# vac.net
KiCad netlist of a schematic drawn in EAGLE
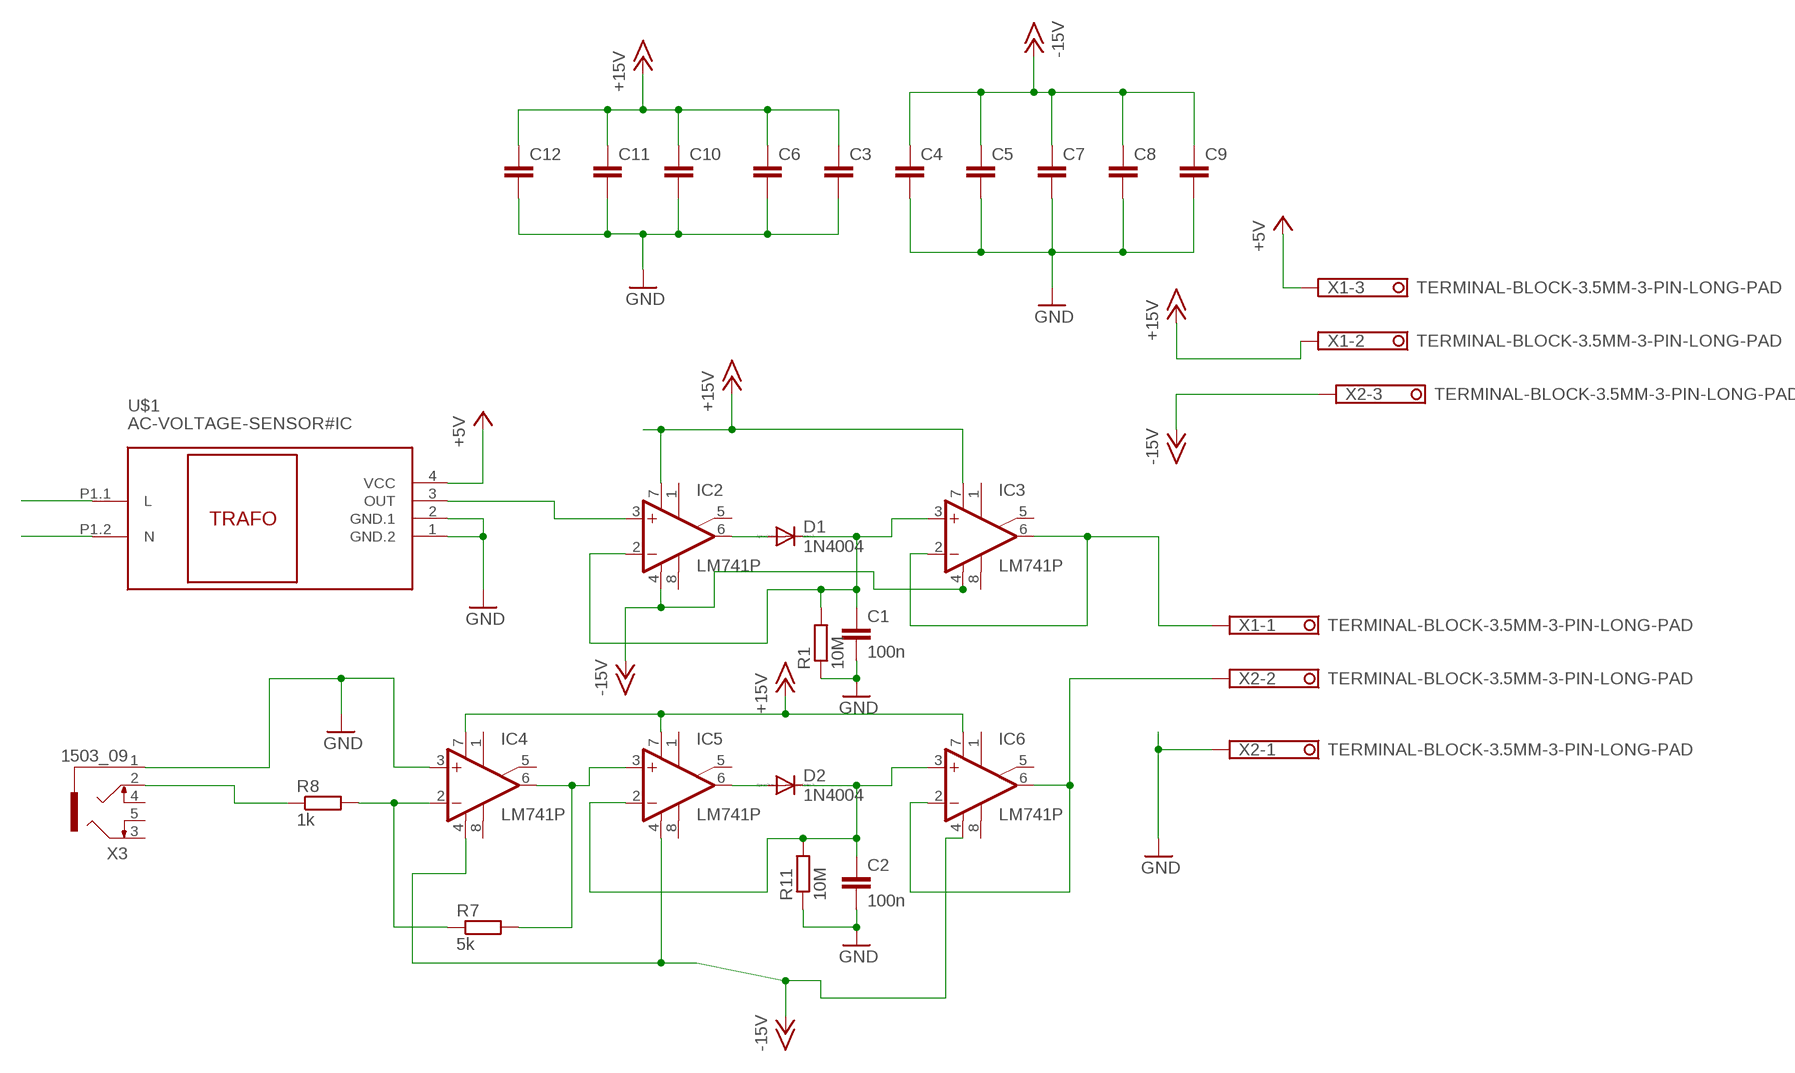
[diagram p0: schematic, sheet 1]

(export (version "E")
  (design (tool "Eeschema 10.0.6"))
  (components
    (comp (ref "C1")
      (value "100n")
      (footprint "eagle-import:C7.5B5")
      (libsource (lib "eagle-import") (part "C7.5/5"))
    )
    (comp (ref "C2")
      (value "100n")
      (footprint "eagle-import:C7.5B5")
      (libsource (lib "eagle-import") (part "C7.5/5"))
    )
    (comp (ref "C3")
      (value "C-EU050-030X075")
      (footprint "eagle-import:C050-030X075")
      (libsource (lib "eagle-import") (part "C-EU050-030X075"))
    )
    (comp (ref "C4")
      (value "C-EU050-030X075")
      (footprint "eagle-import:C050-030X075")
      (libsource (lib "eagle-import") (part "C-EU050-030X075"))
    )
    (comp (ref "C5")
      (value "C-EU050-030X075")
      (footprint "eagle-import:C050-030X075")
      (libsource (lib "eagle-import") (part "C-EU050-030X075"))
    )
    (comp (ref "C6")
      (value "C-EU050-030X075")
      (footprint "eagle-import:C050-030X075")
      (libsource (lib "eagle-import") (part "C-EU050-030X075"))
    )
    (comp (ref "C7")
      (value "C-EU050-030X075")
      (footprint "eagle-import:C050-030X075")
      (libsource (lib "eagle-import") (part "C-EU050-030X075"))
    )
    (comp (ref "C8")
      (value "C-EU050-030X075")
      (footprint "eagle-import:C050-030X075")
      (libsource (lib "eagle-import") (part "C-EU050-030X075"))
    )
    (comp (ref "C9")
      (value "C-EU050-030X075")
      (footprint "eagle-import:C050-030X075")
      (libsource (lib "eagle-import") (part "C-EU050-030X075"))
    )
    (comp (ref "C10")
      (value "C-EU050-030X075")
      (footprint "eagle-import:C050-030X075")
      (libsource (lib "eagle-import") (part "C-EU050-030X075"))
    )
    (comp (ref "C11")
      (value "C-EU050-030X075")
      (footprint "eagle-import:C050-030X075")
      (libsource (lib "eagle-import") (part "C-EU050-030X075"))
    )
    (comp (ref "C12")
      (value "C-EU050-030X075")
      (footprint "eagle-import:C050-030X075")
      (libsource (lib "eagle-import") (part "C-EU050-030X075"))
    )
    (comp (ref "D1")
      (value "1N4004")
      (footprint "eagle-import:DO41-10")
      (libsource (lib "eagle-import") (part "1N4004"))
    )
    (comp (ref "D2")
      (value "1N4004")
      (footprint "eagle-import:DO41-10")
      (libsource (lib "eagle-import") (part "1N4004"))
    )
    (comp (ref "IC2")
      (value "LM741P")
      (footprint "eagle-import:DIL08")
      (libsource (lib "eagle-import") (part "741PLM"))
    )
    (comp (ref "IC3")
      (value "LM741P")
      (footprint "eagle-import:DIL08")
      (libsource (lib "eagle-import") (part "741PLM"))
    )
    (comp (ref "IC4")
      (value "LM741P")
      (footprint "eagle-import:DIL08")
      (libsource (lib "eagle-import") (part "741PLM"))
    )
    (comp (ref "IC5")
      (value "LM741P")
      (footprint "eagle-import:DIL08")
      (libsource (lib "eagle-import") (part "741PLM"))
    )
    (comp (ref "IC6")
      (value "LM741P")
      (footprint "eagle-import:DIL08")
      (libsource (lib "eagle-import") (part "741PLM"))
    )
    (comp (ref "R1")
      (value "10M")
      (footprint "eagle-import:0207_10")
      (libsource (lib "eagle-import") (part "R-EU_0207/10"))
    )
    (comp (ref "R7")
      (value "5k")
      (footprint "eagle-import:0207_10")
      (libsource (lib "eagle-import") (part "R-EU_0207/10"))
    )
    (comp (ref "R8")
      (value "1k")
      (footprint "eagle-import:0207_10")
      (libsource (lib "eagle-import") (part "R-EU_0207/10"))
    )
    (comp (ref "R11")
      (value "10M")
      (footprint "eagle-import:0207_10")
      (libsource (lib "eagle-import") (part "R-EU_0207/10"))
    )
    (comp (ref "U$1")
      (value "AC-VOLTAGE-SENSOR#IC")
      (footprint "eagle-import:AC-VOLTAGE-SENSOR#IC")
      (libsource (lib "eagle-import") (part "AC-VOLTAGE-SENSOR#IC"))
    )
    (comp (ref "X1")
      (value "TERMINAL-BLOCK-3.5MM-3-PIN-LONG-PAD")
      (footprint "eagle-import:TERMINAL-BLOCK-3-PIN-3.5MM-LONG-PAD")
      (libsource (lib "eagle-import") (part "TERMINAL-BLOCK-3.5MM-3-PIN-LONG-PAD"))
    )
    (comp (ref "X2")
      (value "TERMINAL-BLOCK-3.5MM-3-PIN-LONG-PAD")
      (footprint "eagle-import:TERMINAL-BLOCK-3-PIN-3.5MM-LONG-PAD")
      (libsource (lib "eagle-import") (part "TERMINAL-BLOCK-3.5MM-3-PIN-LONG-PAD"))
    )
    (comp (ref "X3")
      (value "1503_09")
      (footprint "eagle-import:1503_09")
      (libsource (lib "eagle-import") (part "1503_09"))
    )
  )
  (nets
    (net (code "1") (name "+5V") (class "Default")
      (node (ref "U$1") (pin "4") (pinfunction "VCC_4") (pintype "power_in"))
      (node (ref "X1") (pin "3") (pinfunction "K_3") (pintype "passive"))
    )
    (net (code "2") (name "+15V") (class "Default")
      (node (ref "C10") (pin "1") (pinfunction "1_1") (pintype "passive"))
      (node (ref "C11") (pin "1") (pinfunction "1_1") (pintype "passive"))
      (node (ref "C12") (pin "1") (pinfunction "1_1") (pintype "passive"))
      (node (ref "C3") (pin "1") (pinfunction "1_1") (pintype "passive"))
      (node (ref "C6") (pin "1") (pinfunction "1_1") (pintype "passive"))
      (node (ref "IC2") (pin "7") (pinfunction "V+_7") (pintype "power_in"))
      (node (ref "IC3") (pin "7") (pinfunction "V+_7") (pintype "power_in"))
      (node (ref "IC4") (pin "7") (pinfunction "V+_7") (pintype "power_in"))
      (node (ref "IC5") (pin "7") (pinfunction "V+_7") (pintype "power_in"))
      (node (ref "IC6") (pin "7") (pinfunction "V+_7") (pintype "power_in"))
      (node (ref "X1") (pin "2") (pinfunction "K_2") (pintype "passive"))
    )
    (net (code "3") (name "-15V") (class "Default")
      (node (ref "C4") (pin "1") (pinfunction "1_1") (pintype "passive"))
      (node (ref "C5") (pin "1") (pinfunction "1_1") (pintype "passive"))
      (node (ref "C7") (pin "1") (pinfunction "1_1") (pintype "passive"))
      (node (ref "C8") (pin "1") (pinfunction "1_1") (pintype "passive"))
      (node (ref "C9") (pin "1") (pinfunction "1_1") (pintype "passive"))
      (node (ref "IC2") (pin "4") (pinfunction "V-_4") (pintype "power_in"))
      (node (ref "IC3") (pin "4") (pinfunction "V-_4") (pintype "power_in"))
      (node (ref "IC4") (pin "4") (pinfunction "V-_4") (pintype "power_in"))
      (node (ref "IC5") (pin "4") (pinfunction "V-_4") (pintype "power_in"))
      (node (ref "IC6") (pin "4") (pinfunction "V-_4") (pintype "power_in"))
      (node (ref "X2") (pin "3") (pinfunction "K_3") (pintype "passive"))
    )
    (net (code "4") (name "GND") (class "Default")
      (node (ref "C1") (pin "2") (pinfunction "2_2") (pintype "passive"))
      (node (ref "C10") (pin "2") (pinfunction "2_2") (pintype "passive"))
      (node (ref "C11") (pin "2") (pinfunction "2_2") (pintype "passive"))
      (node (ref "C12") (pin "2") (pinfunction "2_2") (pintype "passive"))
      (node (ref "C2") (pin "2") (pinfunction "2_2") (pintype "passive"))
      (node (ref "C3") (pin "2") (pinfunction "2_2") (pintype "passive"))
      (node (ref "C4") (pin "2") (pinfunction "2_2") (pintype "passive"))
      (node (ref "C5") (pin "2") (pinfunction "2_2") (pintype "passive"))
      (node (ref "C6") (pin "2") (pinfunction "2_2") (pintype "passive"))
      (node (ref "C7") (pin "2") (pinfunction "2_2") (pintype "passive"))
      (node (ref "C8") (pin "2") (pinfunction "2_2") (pintype "passive"))
      (node (ref "C9") (pin "2") (pinfunction "2_2") (pintype "passive"))
      (node (ref "IC4") (pin "3") (pinfunction "+IN_3") (pintype "input"))
      (node (ref "R1") (pin "1") (pinfunction "1_1") (pintype "passive"))
      (node (ref "R11") (pin "1") (pinfunction "1_1") (pintype "passive"))
      (node (ref "U$1") (pin "1") (pinfunction "GND.2_1") (pintype "power_in"))
      (node (ref "U$1") (pin "2") (pinfunction "GND.1_2") (pintype "power_in"))
      (node (ref "X2") (pin "1") (pinfunction "K_1") (pintype "passive"))
      (node (ref "X3") (pin "1") (pinfunction "1_1") (pintype "passive"))
    )
    (net (code "5") (name "Net-(IC2-+IN)") (class "Default")
      (node (ref "IC2") (pin "3") (pinfunction "+IN_3") (pintype "input"))
      (node (ref "U$1") (pin "3") (pinfunction "OUT_3") (pintype "output"))
    )
    (net (code "6") (name "Net-(IC2--IN)") (class "Default")
      (node (ref "C1") (pin "1") (pinfunction "1_1") (pintype "passive"))
      (node (ref "D1") (pin "C") (pinfunction "C_C") (pintype "passive"))
      (node (ref "IC2") (pin "2") (pinfunction "-IN_2") (pintype "input"))
      (node (ref "IC3") (pin "3") (pinfunction "+IN_3") (pintype "input"))
      (node (ref "R1") (pin "2") (pinfunction "2_2") (pintype "passive"))
    )
    (net (code "7") (name "Net-(IC2-OUT)") (class "Default")
      (node (ref "D1") (pin "A") (pinfunction "A_A") (pintype "passive"))
      (node (ref "IC2") (pin "6") (pinfunction "OUT_6") (pintype "output"))
    )
    (net (code "8") (name "Net-(IC3--IN)") (class "Default")
      (node (ref "IC3") (pin "2") (pinfunction "-IN_2") (pintype "input"))
      (node (ref "IC3") (pin "6") (pinfunction "OUT_6") (pintype "output"))
      (node (ref "X1") (pin "1") (pinfunction "K_1") (pintype "passive"))
    )
    (net (code "9") (name "Net-(IC4--IN)") (class "Default")
      (node (ref "IC4") (pin "2") (pinfunction "-IN_2") (pintype "input"))
      (node (ref "R7") (pin "1") (pinfunction "1_1") (pintype "passive"))
      (node (ref "R8") (pin "2") (pinfunction "2_2") (pintype "passive"))
    )
    (net (code "10") (name "Net-(IC4-OUT)") (class "Default")
      (node (ref "IC4") (pin "6") (pinfunction "OUT_6") (pintype "output"))
      (node (ref "IC5") (pin "3") (pinfunction "+IN_3") (pintype "input"))
      (node (ref "R7") (pin "2") (pinfunction "2_2") (pintype "passive"))
    )
    (net (code "11") (name "Net-(IC5--IN)") (class "Default")
      (node (ref "C2") (pin "1") (pinfunction "1_1") (pintype "passive"))
      (node (ref "D2") (pin "C") (pinfunction "C_C") (pintype "passive"))
      (node (ref "IC5") (pin "2") (pinfunction "-IN_2") (pintype "input"))
      (node (ref "IC6") (pin "3") (pinfunction "+IN_3") (pintype "input"))
      (node (ref "R11") (pin "2") (pinfunction "2_2") (pintype "passive"))
    )
    (net (code "12") (name "Net-(IC5-OUT)") (class "Default")
      (node (ref "D2") (pin "A") (pinfunction "A_A") (pintype "passive"))
      (node (ref "IC5") (pin "6") (pinfunction "OUT_6") (pintype "output"))
    )
    (net (code "13") (name "Net-(IC6--IN)") (class "Default")
      (node (ref "IC6") (pin "2") (pinfunction "-IN_2") (pintype "input"))
      (node (ref "IC6") (pin "6") (pinfunction "OUT_6") (pintype "output"))
      (node (ref "X2") (pin "2") (pinfunction "K_2") (pintype "passive"))
    )
    (net (code "14") (name "Net-(R8-Pad1)") (class "Default")
      (node (ref "R8") (pin "1") (pinfunction "1_1") (pintype "passive"))
      (node (ref "X3") (pin "2") (pinfunction "2_2") (pintype "passive"))
    )
    (net (code "15") (name "unconnected-(IC2-ON1-Pad1)") (class "Default")
      (node (ref "IC2") (pin "1") (pinfunction "ON1_1") (pintype "passive"))
    )
    (net (code "16") (name "unconnected-(IC2-ON2-Pad5)") (class "Default")
      (node (ref "IC2") (pin "5") (pinfunction "ON2_5") (pintype "passive"))
    )
    (net (code "17") (name "unconnected-(IC2-OPT-Pad8)") (class "Default")
      (node (ref "IC2") (pin "8") (pinfunction "OPT_8") (pintype "passive"))
    )
    (net (code "18") (name "unconnected-(IC3-ON1-Pad1)") (class "Default")
      (node (ref "IC3") (pin "1") (pinfunction "ON1_1") (pintype "passive"))
    )
    (net (code "19") (name "unconnected-(IC3-ON2-Pad5)") (class "Default")
      (node (ref "IC3") (pin "5") (pinfunction "ON2_5") (pintype "passive"))
    )
    (net (code "20") (name "unconnected-(IC3-OPT-Pad8)") (class "Default")
      (node (ref "IC3") (pin "8") (pinfunction "OPT_8") (pintype "passive"))
    )
    (net (code "21") (name "unconnected-(IC4-ON1-Pad1)") (class "Default")
      (node (ref "IC4") (pin "1") (pinfunction "ON1_1") (pintype "passive"))
    )
    (net (code "22") (name "unconnected-(IC4-ON2-Pad5)") (class "Default")
      (node (ref "IC4") (pin "5") (pinfunction "ON2_5") (pintype "passive"))
    )
    (net (code "23") (name "unconnected-(IC4-OPT-Pad8)") (class "Default")
      (node (ref "IC4") (pin "8") (pinfunction "OPT_8") (pintype "passive"))
    )
    (net (code "24") (name "unconnected-(IC5-ON1-Pad1)") (class "Default")
      (node (ref "IC5") (pin "1") (pinfunction "ON1_1") (pintype "passive"))
    )
    (net (code "25") (name "unconnected-(IC5-ON2-Pad5)") (class "Default")
      (node (ref "IC5") (pin "5") (pinfunction "ON2_5") (pintype "passive"))
    )
    (net (code "26") (name "unconnected-(IC5-OPT-Pad8)") (class "Default")
      (node (ref "IC5") (pin "8") (pinfunction "OPT_8") (pintype "passive"))
    )
    (net (code "27") (name "unconnected-(IC6-ON1-Pad1)") (class "Default")
      (node (ref "IC6") (pin "1") (pinfunction "ON1_1") (pintype "passive"))
    )
    (net (code "28") (name "unconnected-(IC6-ON2-Pad5)") (class "Default")
      (node (ref "IC6") (pin "5") (pinfunction "ON2_5") (pintype "passive"))
    )
    (net (code "29") (name "unconnected-(IC6-OPT-Pad8)") (class "Default")
      (node (ref "IC6") (pin "8") (pinfunction "OPT_8") (pintype "passive"))
    )
    (net (code "30") (name "unconnected-(U$1-L-PadP1.1)") (class "Default")
      (node (ref "U$1") (pin "P1.1") (pinfunction "L_P1.1") (pintype "passive"))
    )
    (net (code "31") (name "unconnected-(U$1-N-PadP1.2)") (class "Default")
      (node (ref "U$1") (pin "P1.2") (pinfunction "N_P1.2") (pintype "passive"))
    )
    (net (code "32") (name "unconnected-(X3-Pad3)") (class "Default")
      (node (ref "X3") (pin "3") (pinfunction "3_3") (pintype "passive"))
    )
    (net (code "33") (name "unconnected-(X3-Pad4)") (class "Default")
      (node (ref "X3") (pin "4") (pinfunction "4_4") (pintype "passive"))
    )
    (net (code "34") (name "unconnected-(X3-Pad5)") (class "Default")
      (node (ref "X3") (pin "5") (pinfunction "5_5") (pintype "passive"))
    )
  )
)
